# TQFP44.net
KiCad netlist of a schematic drawn in EAGLE
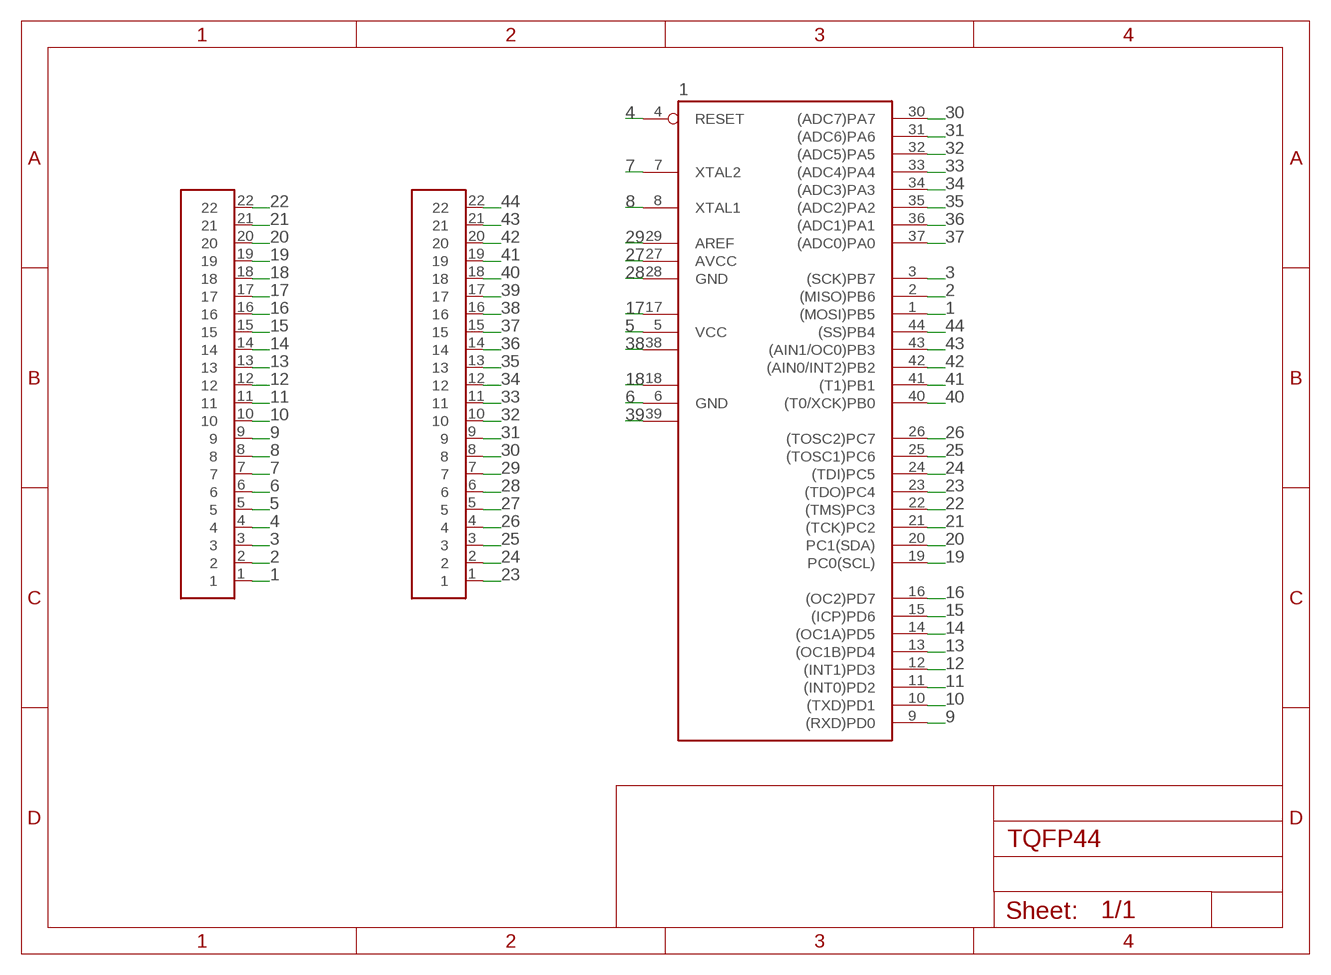
[diagram p0: schematic, sheet 1]

(export (version "E")
  (design (tool "Eeschema 10.0.6"))
  (components
    (comp (ref "1")
      (value "MEGA32-A")
      (footprint "eagle-import:TQFP44")
      (fields (field (name "MPN") "ATMEGA32-16AU"))
      (libsource (lib "eagle-import") (part "MEGA32-A"))
    )
    (comp (ref "2")
      (value "1X22THM")
      (footprint "eagle-import:1X22")
      (libsource (lib "eagle-import") (part "1X22THM"))
    )
    (comp (ref "U$3")
      (value "1X22THM")
      (footprint "eagle-import:1X22")
      (libsource (lib "eagle-import") (part "1X22THM"))
    )
  )
  (nets
    (net (code "1") (name "/1") (class "Default")
      (node (ref "1") (pin "1") (pinfunction "(MOSI)PB5_1") (pintype "bidirectional"))
      (node (ref "2") (pin "1") (pinfunction "1_1") (pintype "bidirectional"))
    )
    (net (code "2") (name "/2") (class "Default")
      (node (ref "1") (pin "2") (pinfunction "(MISO)PB6_2") (pintype "bidirectional"))
      (node (ref "2") (pin "2") (pinfunction "2_2") (pintype "bidirectional"))
    )
    (net (code "3") (name "/3") (class "Default")
      (node (ref "1") (pin "3") (pinfunction "(SCK)PB7_3") (pintype "bidirectional"))
      (node (ref "2") (pin "3") (pinfunction "3_3") (pintype "bidirectional"))
    )
    (net (code "4") (name "/4") (class "Default")
      (node (ref "1") (pin "4") (pinfunction "RESET_4") (pintype "input"))
      (node (ref "2") (pin "4") (pinfunction "4_4") (pintype "bidirectional"))
    )
    (net (code "5") (name "/5") (class "Default")
      (node (ref "1") (pin "5") (pinfunction "VCC_5") (pintype "power_in"))
      (node (ref "2") (pin "5") (pinfunction "5_5") (pintype "bidirectional"))
    )
    (net (code "6") (name "/6") (class "Default")
      (node (ref "1") (pin "6") (pinfunction "GND_6") (pintype "power_in"))
      (node (ref "2") (pin "6") (pinfunction "6_6") (pintype "bidirectional"))
    )
    (net (code "7") (name "/7") (class "Default")
      (node (ref "1") (pin "7") (pinfunction "XTAL2_7") (pintype "bidirectional"))
      (node (ref "2") (pin "7") (pinfunction "7_7") (pintype "bidirectional"))
    )
    (net (code "8") (name "/8") (class "Default")
      (node (ref "1") (pin "8") (pinfunction "XTAL1_8") (pintype "bidirectional"))
      (node (ref "2") (pin "8") (pinfunction "8_8") (pintype "bidirectional"))
    )
    (net (code "9") (name "/9") (class "Default")
      (node (ref "1") (pin "9") (pinfunction "(RXD)PD0_9") (pintype "bidirectional"))
      (node (ref "2") (pin "9") (pinfunction "9_9") (pintype "bidirectional"))
    )
    (net (code "10") (name "/10") (class "Default")
      (node (ref "1") (pin "10") (pinfunction "(TXD)PD1_10") (pintype "bidirectional"))
      (node (ref "2") (pin "10") (pinfunction "10_10") (pintype "bidirectional"))
    )
    (net (code "11") (name "/11") (class "Default")
      (node (ref "1") (pin "11") (pinfunction "(INT0)PD2_11") (pintype "bidirectional"))
      (node (ref "2") (pin "11") (pinfunction "11_11") (pintype "bidirectional"))
    )
    (net (code "12") (name "/12") (class "Default")
      (node (ref "1") (pin "12") (pinfunction "(INT1)PD3_12") (pintype "bidirectional"))
      (node (ref "2") (pin "12") (pinfunction "12_12") (pintype "bidirectional"))
    )
    (net (code "13") (name "/13") (class "Default")
      (node (ref "1") (pin "13") (pinfunction "(OC1B)PD4_13") (pintype "bidirectional"))
      (node (ref "2") (pin "13") (pinfunction "13_13") (pintype "bidirectional"))
    )
    (net (code "14") (name "/14") (class "Default")
      (node (ref "1") (pin "14") (pinfunction "(OC1A)PD5_14") (pintype "bidirectional"))
      (node (ref "2") (pin "14") (pinfunction "14_14") (pintype "bidirectional"))
    )
    (net (code "15") (name "/15") (class "Default")
      (node (ref "1") (pin "15") (pinfunction "(ICP)PD6_15") (pintype "bidirectional"))
      (node (ref "2") (pin "15") (pinfunction "15_15") (pintype "bidirectional"))
    )
    (net (code "16") (name "/16") (class "Default")
      (node (ref "1") (pin "16") (pinfunction "(OC2)PD7_16") (pintype "bidirectional"))
      (node (ref "2") (pin "16") (pinfunction "16_16") (pintype "bidirectional"))
    )
    (net (code "17") (name "/17") (class "Default")
      (node (ref "1") (pin "17") (pinfunction "VCC1_17") (pintype "power_in"))
      (node (ref "2") (pin "17") (pinfunction "17_17") (pintype "bidirectional"))
    )
    (net (code "18") (name "/18") (class "Default")
      (node (ref "1") (pin "18") (pinfunction "GND1_18") (pintype "power_in"))
      (node (ref "2") (pin "18") (pinfunction "18_18") (pintype "bidirectional"))
    )
    (net (code "19") (name "/19") (class "Default")
      (node (ref "1") (pin "19") (pinfunction "PC0(SCL)_19") (pintype "bidirectional"))
      (node (ref "2") (pin "19") (pinfunction "19_19") (pintype "bidirectional"))
    )
    (net (code "20") (name "/20") (class "Default")
      (node (ref "1") (pin "20") (pinfunction "PC1(SDA)_20") (pintype "bidirectional"))
      (node (ref "2") (pin "20") (pinfunction "20_20") (pintype "bidirectional"))
    )
    (net (code "21") (name "/21") (class "Default")
      (node (ref "1") (pin "21") (pinfunction "(TCK)PC2_21") (pintype "bidirectional"))
      (node (ref "2") (pin "21") (pinfunction "21_21") (pintype "bidirectional"))
    )
    (net (code "22") (name "/22") (class "Default")
      (node (ref "1") (pin "22") (pinfunction "(TMS)PC3_22") (pintype "bidirectional"))
      (node (ref "2") (pin "22") (pinfunction "22_22") (pintype "bidirectional"))
    )
    (net (code "23") (name "/23") (class "Default")
      (node (ref "1") (pin "23") (pinfunction "(TDO)PC4_23") (pintype "bidirectional"))
      (node (ref "U$3") (pin "1") (pinfunction "1_1") (pintype "bidirectional"))
    )
    (net (code "24") (name "/24") (class "Default")
      (node (ref "1") (pin "24") (pinfunction "(TDI)PC5_24") (pintype "bidirectional"))
      (node (ref "U$3") (pin "2") (pinfunction "2_2") (pintype "bidirectional"))
    )
    (net (code "25") (name "/25") (class "Default")
      (node (ref "1") (pin "25") (pinfunction "(TOSC1)PC6_25") (pintype "bidirectional"))
      (node (ref "U$3") (pin "3") (pinfunction "3_3") (pintype "bidirectional"))
    )
    (net (code "26") (name "/26") (class "Default")
      (node (ref "1") (pin "26") (pinfunction "(TOSC2)PC7_26") (pintype "bidirectional"))
      (node (ref "U$3") (pin "4") (pinfunction "4_4") (pintype "bidirectional"))
    )
    (net (code "27") (name "/27") (class "Default")
      (node (ref "1") (pin "27") (pinfunction "AVCC_27") (pintype "power_in"))
      (node (ref "U$3") (pin "5") (pinfunction "5_5") (pintype "bidirectional"))
    )
    (net (code "28") (name "/28") (class "Default")
      (node (ref "1") (pin "28") (pinfunction "GND_28") (pintype "power_in"))
      (node (ref "U$3") (pin "6") (pinfunction "6_6") (pintype "bidirectional"))
    )
    (net (code "29") (name "/29") (class "Default")
      (node (ref "1") (pin "29") (pinfunction "AREF_29") (pintype "passive"))
      (node (ref "U$3") (pin "7") (pinfunction "7_7") (pintype "bidirectional"))
    )
    (net (code "30") (name "/30") (class "Default")
      (node (ref "1") (pin "30") (pinfunction "(ADC7)PA7_30") (pintype "bidirectional"))
      (node (ref "U$3") (pin "8") (pinfunction "8_8") (pintype "bidirectional"))
    )
    (net (code "31") (name "/31") (class "Default")
      (node (ref "1") (pin "31") (pinfunction "(ADC6)PA6_31") (pintype "bidirectional"))
      (node (ref "U$3") (pin "9") (pinfunction "9_9") (pintype "bidirectional"))
    )
    (net (code "32") (name "/32") (class "Default")
      (node (ref "1") (pin "32") (pinfunction "(ADC5)PA5_32") (pintype "bidirectional"))
      (node (ref "U$3") (pin "10") (pinfunction "10_10") (pintype "bidirectional"))
    )
    (net (code "33") (name "/33") (class "Default")
      (node (ref "1") (pin "33") (pinfunction "(ADC4)PA4_33") (pintype "bidirectional"))
      (node (ref "U$3") (pin "11") (pinfunction "11_11") (pintype "bidirectional"))
    )
    (net (code "34") (name "/34") (class "Default")
      (node (ref "1") (pin "34") (pinfunction "(ADC3)PA3_34") (pintype "bidirectional"))
      (node (ref "U$3") (pin "12") (pinfunction "12_12") (pintype "bidirectional"))
    )
    (net (code "35") (name "/35") (class "Default")
      (node (ref "1") (pin "35") (pinfunction "(ADC2)PA2_35") (pintype "bidirectional"))
      (node (ref "U$3") (pin "13") (pinfunction "13_13") (pintype "bidirectional"))
    )
    (net (code "36") (name "/36") (class "Default")
      (node (ref "1") (pin "36") (pinfunction "(ADC1)PA1_36") (pintype "bidirectional"))
      (node (ref "U$3") (pin "14") (pinfunction "14_14") (pintype "bidirectional"))
    )
    (net (code "37") (name "/37") (class "Default")
      (node (ref "1") (pin "37") (pinfunction "(ADC0)PA0_37") (pintype "bidirectional"))
      (node (ref "U$3") (pin "15") (pinfunction "15_15") (pintype "bidirectional"))
    )
    (net (code "38") (name "/38") (class "Default")
      (node (ref "1") (pin "38") (pinfunction "VCC2_38") (pintype "power_in"))
      (node (ref "U$3") (pin "16") (pinfunction "16_16") (pintype "bidirectional"))
    )
    (net (code "39") (name "/39") (class "Default")
      (node (ref "1") (pin "39") (pinfunction "GND2_39") (pintype "power_in"))
      (node (ref "U$3") (pin "17") (pinfunction "17_17") (pintype "bidirectional"))
    )
    (net (code "40") (name "/40") (class "Default")
      (node (ref "1") (pin "40") (pinfunction "(T0/XCK)PB0_40") (pintype "bidirectional"))
      (node (ref "U$3") (pin "18") (pinfunction "18_18") (pintype "bidirectional"))
    )
    (net (code "41") (name "/41") (class "Default")
      (node (ref "1") (pin "41") (pinfunction "(T1)PB1_41") (pintype "bidirectional"))
      (node (ref "U$3") (pin "19") (pinfunction "19_19") (pintype "bidirectional"))
    )
    (net (code "42") (name "/42") (class "Default")
      (node (ref "1") (pin "42") (pinfunction "(AIN0/INT2)PB2_42") (pintype "bidirectional"))
      (node (ref "U$3") (pin "20") (pinfunction "20_20") (pintype "bidirectional"))
    )
    (net (code "43") (name "/43") (class "Default")
      (node (ref "1") (pin "43") (pinfunction "(AIN1/OC0)PB3_43") (pintype "bidirectional"))
      (node (ref "U$3") (pin "21") (pinfunction "21_21") (pintype "bidirectional"))
    )
    (net (code "44") (name "/44") (class "Default")
      (node (ref "1") (pin "44") (pinfunction "(SS)PB4_44") (pintype "bidirectional"))
      (node (ref "U$3") (pin "22") (pinfunction "22_22") (pintype "bidirectional"))
    )
  )
)
